# SparkFun_MicroPressure_Sensor.net
KiCad netlist of a schematic drawn in EAGLE
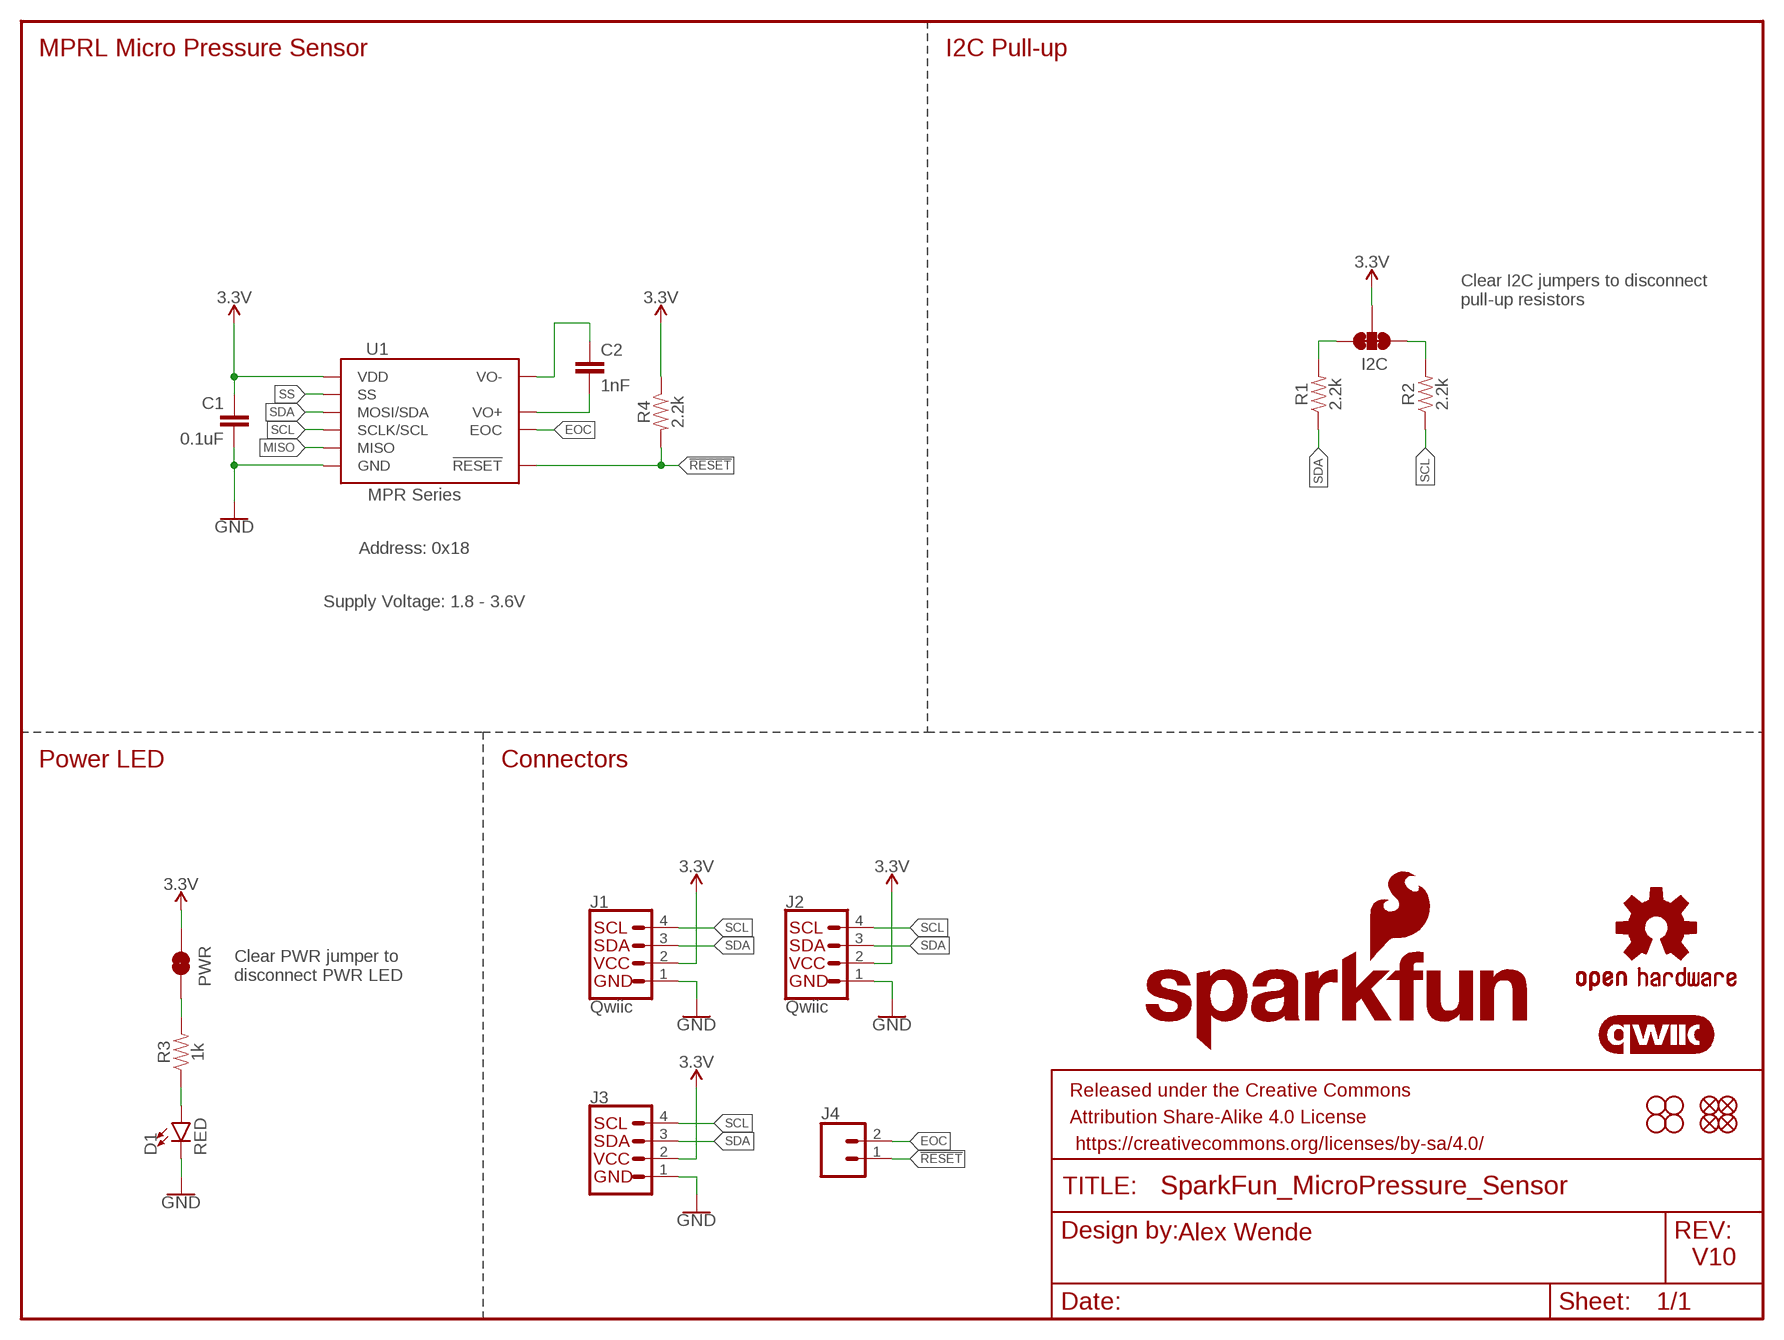
[diagram p0: schematic, sheet 1]

(export (version "E")
  (design (tool "Eeschema 10.0.6"))
  (components
    (comp (ref "C1")
      (value "0.1uF")
      (footprint "eagle-import:0603")
      (libsource (lib "eagle-import") (part "0.1UF-0603-25V-(+80/-20%)"))
    )
    (comp (ref "C2")
      (value "1nF")
      (footprint "eagle-import:0603")
      (libsource (lib "eagle-import") (part "1.0NF/1000PF-0603-50V-10%"))
    )
    (comp (ref "D1")
      (value "RED")
      (footprint "eagle-import:LED-0603")
      (libsource (lib "eagle-import") (part "LED-RED0603"))
    )
    (comp (ref "FD1")
      (value "FIDUCIALUFIDUCIAL")
      (footprint "eagle-import:FIDUCIAL-MICRO")
      (libsource (lib "eagle-import") (part "FIDUCIALUFIDUCIAL"))
    )
    (comp (ref "FD2")
      (value "FIDUCIALUFIDUCIAL")
      (footprint "eagle-import:FIDUCIAL-MICRO")
      (libsource (lib "eagle-import") (part "FIDUCIALUFIDUCIAL"))
    )
    (comp (ref "FD3")
      (value "FIDUCIALUFIDUCIAL")
      (footprint "eagle-import:FIDUCIAL-MICRO")
      (libsource (lib "eagle-import") (part "FIDUCIALUFIDUCIAL"))
    )
    (comp (ref "FD4")
      (value "FIDUCIALUFIDUCIAL")
      (footprint "eagle-import:FIDUCIAL-MICRO")
      (libsource (lib "eagle-import") (part "FIDUCIALUFIDUCIAL"))
    )
    (comp (ref "FRAME1")
      (value "FRAME-LETTER")
      (footprint "eagle-import:CREATIVE_COMMONS")
      (libsource (lib "eagle-import") (part "FRAME-LETTER"))
    )
    (comp (ref "H1")
      (value "STAND-OFF")
      (footprint "eagle-import:STAND-OFF")
      (libsource (lib "eagle-import") (part "STAND-OFF"))
    )
    (comp (ref "H2")
      (value "STAND-OFF")
      (footprint "eagle-import:STAND-OFF")
      (libsource (lib "eagle-import") (part "STAND-OFF"))
    )
    (comp (ref "H3")
      (value "STAND-OFF")
      (footprint "eagle-import:STAND-OFF")
      (libsource (lib "eagle-import") (part "STAND-OFF"))
    )
    (comp (ref "H4")
      (value "STAND-OFF")
      (footprint "eagle-import:STAND-OFF")
      (libsource (lib "eagle-import") (part "STAND-OFF"))
    )
    (comp (ref "I2C")
      (value "JUMPER-SMT_3_2-NC_TRACE_SILK")
      (footprint "eagle-import:SMT-JUMPER_3_2-NC_TRACE_SILK")
      (libsource (lib "eagle-import") (part "JUMPER-SMT_3_2-NC_TRACE_SILK"))
    )
    (comp (ref "J1")
      (value "Qwiic")
      (footprint "eagle-import:JST04_1MM_RA")
      (libsource (lib "eagle-import") (part "I2C_STANDARDQWIIC"))
    )
    (comp (ref "J2")
      (value "Qwiic")
      (footprint "eagle-import:JST04_1MM_RA")
      (libsource (lib "eagle-import") (part "I2C_STANDARDQWIIC"))
    )
    (comp (ref "J3")
      (value "I2C_STANDARD_NO_SILK")
      (footprint "eagle-import:1X04_NO_SILK")
      (libsource (lib "eagle-import") (part "I2C_STANDARD_NO_SILK"))
    )
    (comp (ref "J4")
      (value "CONN_021X02_NO_SILK")
      (footprint "eagle-import:1X02_NO_SILK")
      (libsource (lib "eagle-import") (part "CONN_021X02_NO_SILK"))
    )
    (comp (ref "LOGO1")
      (value "QWIIC_LOGO_5MM")
      (footprint "eagle-import:QWIIC_5MM")
      (libsource (lib "eagle-import") (part "QWIIC_LOGO_5MM"))
    )
    (comp (ref "LOGO2")
      (value "OSHW-LOGOS")
      (footprint "eagle-import:OSHW-LOGO-S")
      (libsource (lib "eagle-import") (part "OSHW-LOGOS"))
    )
    (comp (ref "LOGO3")
      (value "SFE_LOGO_NAME_FLAME.1_INCH")
      (footprint "eagle-import:SFE_LOGO_NAME_FLAME_.1")
      (libsource (lib "eagle-import") (part "SFE_LOGO_NAME_FLAME.1_INCH"))
    )
    (comp (ref "PWR")
      (value "JUMPER-SMT_2_NC_TRACE_SILK")
      (footprint "eagle-import:SMT-JUMPER_2_NC_TRACE_SILK")
      (libsource (lib "eagle-import") (part "JUMPER-SMT_2_NC_TRACE_SILK"))
    )
    (comp (ref "R1")
      (value "2.2k")
      (footprint "eagle-import:0603")
      (libsource (lib "eagle-import") (part "2.2KOHM-0603-1/10W-1%"))
    )
    (comp (ref "R2")
      (value "2.2k")
      (footprint "eagle-import:0603")
      (libsource (lib "eagle-import") (part "2.2KOHM-0603-1/10W-1%"))
    )
    (comp (ref "R3")
      (value "1k")
      (footprint "eagle-import:0603")
      (libsource (lib "eagle-import") (part "1KOHM-0603-1/10W-1%"))
    )
    (comp (ref "R4")
      (value "2.2k")
      (footprint "eagle-import:0603")
      (libsource (lib "eagle-import") (part "2.2KOHM-0603-1/10W-1%"))
    )
    (comp (ref "U1")
      (value "MPR Series")
      (footprint "eagle-import:MPR_SERIES_PRESSURE_I2C")
      (libsource (lib "eagle-import") (part "MPR_SERIES_PRESSURE_I2C"))
    )
  )
  (nets
    (net (code "1") (name "/~{RESET}") (class "Default")
      (node (ref "J4") (pin "1") (pinfunction "1_1") (pintype "passive"))
      (node (ref "R4") (pin "2") (pinfunction "2_2") (pintype "passive"))
      (node (ref "U1") (pin "9") (pinfunction "~{RESET}_9") (pintype "bidirectional"))
    )
    (net (code "2") (name "3.3V") (class "Default")
      (node (ref "C1") (pin "1") (pinfunction "1_1") (pintype "passive"))
      (node (ref "I2C") (pin "2") (pinfunction "2_2") (pintype "passive"))
      (node (ref "J1") (pin "2") (pinfunction "2_2") (pintype "power_in"))
      (node (ref "J2") (pin "2") (pinfunction "2_2") (pintype "power_in"))
      (node (ref "J3") (pin "2") (pinfunction "2_2") (pintype "power_in"))
      (node (ref "PWR") (pin "1") (pinfunction "1_1") (pintype "passive"))
      (node (ref "R4") (pin "1") (pinfunction "1_1") (pintype "passive"))
      (node (ref "U1") (pin "12") (pinfunction "VDD_12") (pintype "bidirectional"))
    )
    (net (code "3") (name "EOC") (class "Default")
      (node (ref "J4") (pin "2") (pinfunction "2_2") (pintype "passive"))
      (node (ref "U1") (pin "8") (pinfunction "EOC_8") (pintype "bidirectional"))
    )
    (net (code "4") (name "GND") (class "Default")
      (node (ref "C1") (pin "2") (pinfunction "2_2") (pintype "passive"))
      (node (ref "D1") (pin "C") (pinfunction "C_C") (pintype "passive"))
      (node (ref "J1") (pin "1") (pinfunction "1_1") (pintype "power_in"))
      (node (ref "J2") (pin "1") (pinfunction "1_1") (pintype "power_in"))
      (node (ref "J3") (pin "1") (pinfunction "1_1") (pintype "power_in"))
      (node (ref "U1") (pin "10") (pinfunction "GND_10") (pintype "bidirectional"))
    )
    (net (code "5") (name "MISO") (class "Default")
      (node (ref "U1") (pin "7") (pinfunction "MISO_7") (pintype "bidirectional"))
    )
    (net (code "6") (name "Net-(D1-PadA)") (class "Default")
      (node (ref "D1") (pin "A") (pinfunction "A_A") (pintype "passive"))
      (node (ref "R3") (pin "1") (pinfunction "1_1") (pintype "passive"))
    )
    (net (code "7") (name "Net-(I2C-Pad1)") (class "Default")
      (node (ref "I2C") (pin "1") (pinfunction "1_1") (pintype "passive"))
      (node (ref "R2") (pin "2") (pinfunction "2_2") (pintype "passive"))
    )
    (net (code "8") (name "Net-(I2C-Pad3)") (class "Default")
      (node (ref "I2C") (pin "3") (pinfunction "3_3") (pintype "passive"))
      (node (ref "R1") (pin "2") (pinfunction "2_2") (pintype "passive"))
    )
    (net (code "9") (name "Net-(PWR-Pad2)") (class "Default")
      (node (ref "PWR") (pin "2") (pinfunction "2_2") (pintype "passive"))
      (node (ref "R3") (pin "2") (pinfunction "2_2") (pintype "passive"))
    )
    (net (code "10") (name "Net-(U1-VO+)") (class "Default")
      (node (ref "C2") (pin "2") (pinfunction "2_2") (pintype "passive"))
      (node (ref "U1") (pin "4") (pinfunction "VO+_4") (pintype "bidirectional"))
    )
    (net (code "11") (name "Net-(U1-VO-)") (class "Default")
      (node (ref "C2") (pin "1") (pinfunction "1_1") (pintype "passive"))
      (node (ref "U1") (pin "6") (pinfunction "VO-_6") (pintype "bidirectional"))
    )
    (net (code "12") (name "SCL") (class "Default")
      (node (ref "J1") (pin "4") (pinfunction "4_4") (pintype "passive"))
      (node (ref "J2") (pin "4") (pinfunction "4_4") (pintype "passive"))
      (node (ref "J3") (pin "4") (pinfunction "4_4") (pintype "passive"))
      (node (ref "R2") (pin "1") (pinfunction "1_1") (pintype "passive"))
      (node (ref "U1") (pin "3") (pinfunction "SCLK/SCL_3") (pintype "bidirectional"))
    )
    (net (code "13") (name "SDA") (class "Default")
      (node (ref "J1") (pin "3") (pinfunction "3_3") (pintype "passive"))
      (node (ref "J2") (pin "3") (pinfunction "3_3") (pintype "passive"))
      (node (ref "J3") (pin "3") (pinfunction "3_3") (pintype "passive"))
      (node (ref "R1") (pin "1") (pinfunction "1_1") (pintype "passive"))
      (node (ref "U1") (pin "2") (pinfunction "MOSI/SDA_2") (pintype "bidirectional"))
    )
    (net (code "14") (name "SS") (class "Default")
      (node (ref "U1") (pin "1") (pinfunction "SS_1") (pintype "bidirectional"))
    )
  )
)
